# mirsot_sch-final.net
KiCad netlist of a schematic drawn in EAGLE
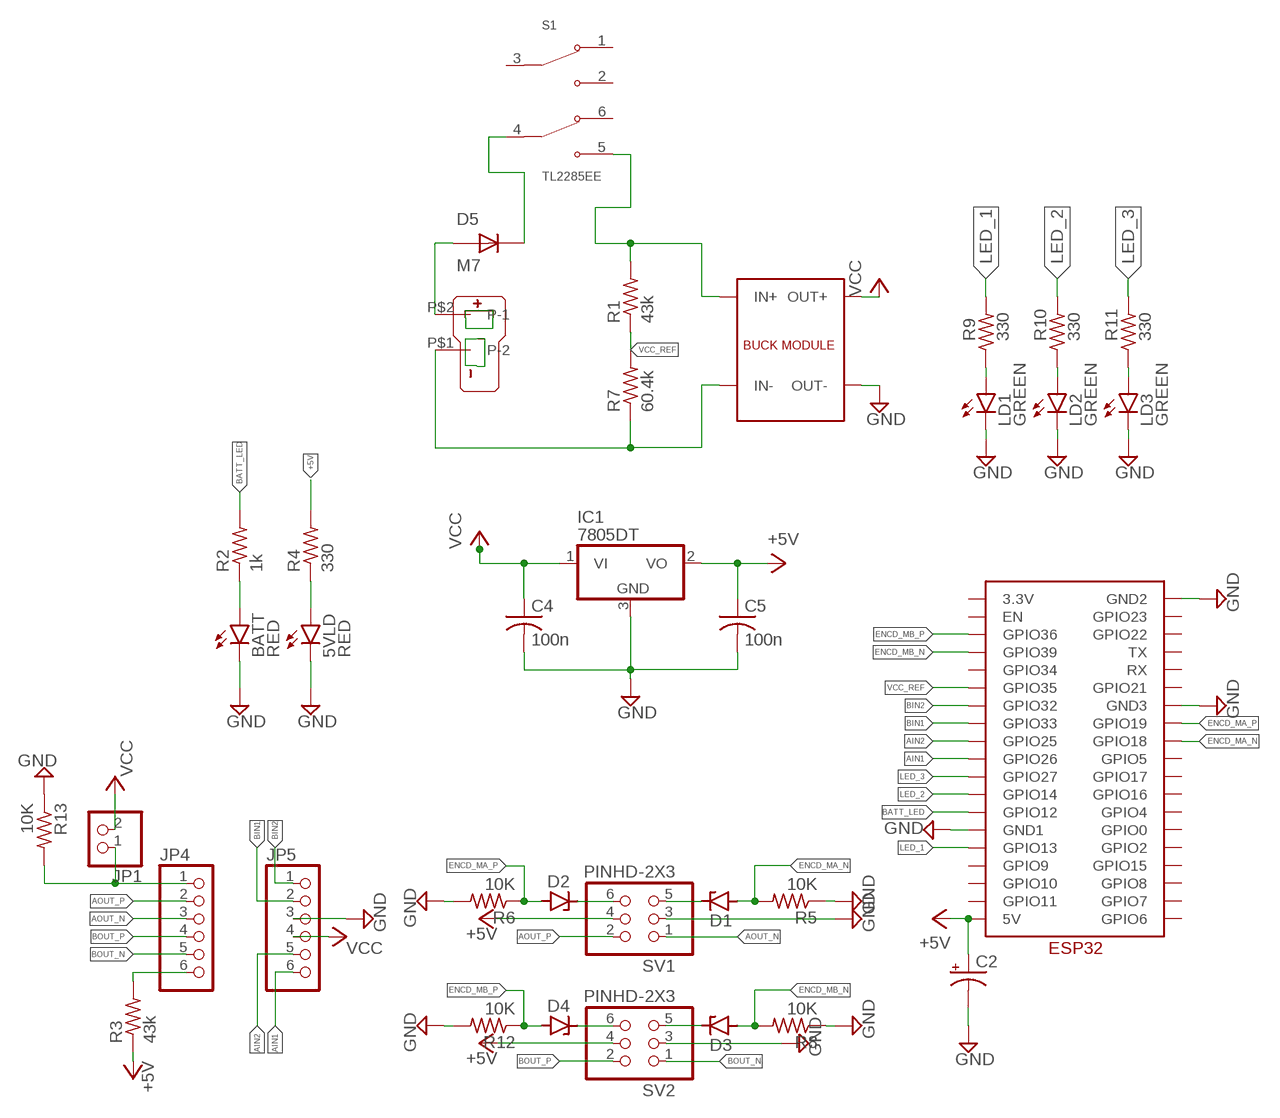
[diagram p0: schematic, sheet 1]

(export (version "E")
  (design (tool "Eeschema 10.0.6"))
  (components
    (comp (ref "5VLD")
      (value "RED")
      (footprint "eagle-import:SML1206")
      (libsource (lib "eagle-import") (part "LEDSML1206"))
    )
    (comp (ref "BATT")
      (value "RED")
      (footprint "eagle-import:SML1206")
      (libsource (lib "eagle-import") (part "LEDSML1206"))
    )
    (comp (ref "C2")
      (value "CPOL-USE2.5-6")
      (footprint "eagle-import:E2,5-6")
      (libsource (lib "eagle-import") (part "CPOL-USE2.5-6"))
    )
    (comp (ref "C4")
      (value "100n")
      (footprint "eagle-import:C0603K")
      (libsource (lib "eagle-import") (part "C-USC0603K"))
    )
    (comp (ref "C5")
      (value "100n")
      (footprint "eagle-import:C0603K")
      (libsource (lib "eagle-import") (part "C-USC0603K"))
    )
    (comp (ref "D1")
      (value "ZENER-DIODEDO34-7")
      (footprint "eagle-import:DO34Z7")
      (libsource (lib "eagle-import") (part "ZENER-DIODEDO34-7"))
    )
    (comp (ref "D2")
      (value "ZENER-DIODEDO34-7")
      (footprint "eagle-import:DO34Z7")
      (libsource (lib "eagle-import") (part "ZENER-DIODEDO34-7"))
    )
    (comp (ref "D3")
      (value "ZENER-DIODEDO34-7")
      (footprint "eagle-import:DO34Z7")
      (libsource (lib "eagle-import") (part "ZENER-DIODEDO34-7"))
    )
    (comp (ref "D4")
      (value "ZENER-DIODEDO34-7")
      (footprint "eagle-import:DO34Z7")
      (libsource (lib "eagle-import") (part "ZENER-DIODEDO34-7"))
    )
    (comp (ref "D5")
      (value "M7")
      (footprint "eagle-import:DIOM505270X240")
      (fields (field (name "MF") "Diotec Semiconductor"))
      (libsource (lib "eagle-import") (part "M7"))
    )
    (comp (ref "IC1")
      (value "7805DT")
      (footprint "eagle-import:TO252")
      (libsource (lib "eagle-import") (part "78DT05"))
    )
    (comp (ref "JP1")
      (value "PINHD-1X2")
      (footprint "eagle-import:1X02")
      (libsource (lib "eagle-import") (part "PINHD-1X2"))
    )
    (comp (ref "JP4")
      (value "PINHD-1X6")
      (footprint "eagle-import:1X06")
      (libsource (lib "eagle-import") (part "PINHD-1X6"))
    )
    (comp (ref "JP5")
      (value "PINHD-1X6")
      (footprint "eagle-import:1X06")
      (libsource (lib "eagle-import") (part "PINHD-1X6"))
    )
    (comp (ref "LD1")
      (value "GREEN")
      (footprint "eagle-import:SML1206")
      (libsource (lib "eagle-import") (part "LEDSML1206"))
    )
    (comp (ref "LD2")
      (value "GREEN")
      (footprint "eagle-import:SML1206")
      (libsource (lib "eagle-import") (part "LEDSML1206"))
    )
    (comp (ref "LD3")
      (value "GREEN")
      (footprint "eagle-import:SML1206")
      (libsource (lib "eagle-import") (part "LEDSML1206"))
    )
    (comp (ref "R1")
      (value "43k")
      (footprint "eagle-import:M1206")
      (libsource (lib "eagle-import") (part "R-US_M1206"))
    )
    (comp (ref "R2")
      (value "1k")
      (footprint "eagle-import:M1206")
      (libsource (lib "eagle-import") (part "R-US_M1206"))
    )
    (comp (ref "R3")
      (value "43k")
      (footprint "eagle-import:M1206")
      (libsource (lib "eagle-import") (part "R-US_M1206"))
    )
    (comp (ref "R4")
      (value "330")
      (footprint "eagle-import:M1206")
      (libsource (lib "eagle-import") (part "R-US_M1206"))
    )
    (comp (ref "R5")
      (value "10K")
      (footprint "eagle-import:M1206")
      (libsource (lib "eagle-import") (part "R-US_M1206"))
    )
    (comp (ref "R6")
      (value "10K")
      (footprint "eagle-import:M1206")
      (libsource (lib "eagle-import") (part "R-US_M1206"))
    )
    (comp (ref "R7")
      (value "60.4k")
      (footprint "eagle-import:M1206")
      (libsource (lib "eagle-import") (part "R-US_M1206"))
    )
    (comp (ref "R8")
      (value "10K")
      (footprint "eagle-import:M1206")
      (libsource (lib "eagle-import") (part "R-US_M1206"))
    )
    (comp (ref "R9")
      (value "330")
      (footprint "eagle-import:M1206")
      (libsource (lib "eagle-import") (part "R-US_M1206"))
    )
    (comp (ref "R10")
      (value "330")
      (footprint "eagle-import:M1206")
      (libsource (lib "eagle-import") (part "R-US_M1206"))
    )
    (comp (ref "R11")
      (value "330")
      (footprint "eagle-import:M1206")
      (libsource (lib "eagle-import") (part "R-US_M1206"))
    )
    (comp (ref "R12")
      (value "10K")
      (footprint "eagle-import:M1206")
      (libsource (lib "eagle-import") (part "R-US_M1206"))
    )
    (comp (ref "R13")
      (value "10K")
      (footprint "eagle-import:M1206")
      (libsource (lib "eagle-import") (part "R-US_M1206"))
    )
    (comp (ref "S1")
      (value "TL2285EE")
      (footprint "eagle-import:SW_TL2285EE")
      (fields (field (name "MF") "E-Switch"))
      (libsource (lib "eagle-import") (part "TL2285EE"))
    )
    (comp (ref "SV1")
      (value "PINHD-2X3")
      (footprint "eagle-import:2X03")
      (libsource (lib "eagle-import") (part "PINHD-2X3"))
    )
    (comp (ref "SV2")
      (value "PINHD-2X3")
      (footprint "eagle-import:2X03")
      (libsource (lib "eagle-import") (part "PINHD-2X3"))
    )
    (comp (ref "U$1")
      (value "T_PLUG_CONNECTOR_H")
      (footprint "eagle-import:T_PLUG_CONNECTOR_H")
      (libsource (lib "eagle-import") (part "T_PLUG_CONNECTOR_H"))
    )
    (comp (ref "U$2")
      (value "ESP32")
      (footprint "eagle-import:ESP32")
      (libsource (lib "eagle-import") (part "ESP32"))
    )
    (comp (ref "U$3")
      (value "BUCK_CONVERTER")
      (footprint "eagle-import:BUCK_CONVERTER")
      (libsource (lib "eagle-import") (part "BUCK_CONVERTER"))
    )
  )
  (nets
    (net (code "1") (name "+5V") (class "Default")
      (node (ref "C2") (pin "+") (pinfunction "+_+") (pintype "passive"))
      (node (ref "C5") (pin "1") (pinfunction "1_1") (pintype "passive"))
      (node (ref "IC1") (pin "2") (pinfunction "VO_2") (pintype "passive"))
      (node (ref "R3") (pin "1") (pinfunction "1_1") (pintype "passive"))
      (node (ref "R4") (pin "2") (pinfunction "2_2") (pintype "passive"))
      (node (ref "SV1") (pin "4") (pinfunction "4_4") (pintype "passive"))
      (node (ref "SV2") (pin "4") (pinfunction "4_4") (pintype "passive"))
      (node (ref "U$2") (pin "5V") (pinfunction "5V_5V") (pintype "bidirectional"))
    )
    (net (code "2") (name "AIN1") (class "Default")
      (node (ref "JP5") (pin "6") (pinfunction "6_6") (pintype "passive"))
      (node (ref "U$2") (pin "GPIO26") (pinfunction "GPIO26_GPIO26") (pintype "bidirectional"))
    )
    (net (code "3") (name "AIN2") (class "Default")
      (node (ref "JP5") (pin "5") (pinfunction "5_5") (pintype "passive"))
      (node (ref "U$2") (pin "GPIO25") (pinfunction "GPIO25_GPIO25") (pintype "bidirectional"))
    )
    (net (code "4") (name "AOUT_N") (class "Default")
      (node (ref "JP4") (pin "3") (pinfunction "3_3") (pintype "passive"))
      (node (ref "SV1") (pin "1") (pinfunction "1_1") (pintype "passive"))
    )
    (net (code "5") (name "AOUT_P") (class "Default")
      (node (ref "JP4") (pin "2") (pinfunction "2_2") (pintype "passive"))
      (node (ref "SV1") (pin "2") (pinfunction "2_2") (pintype "passive"))
    )
    (net (code "6") (name "BATT_LED") (class "Default")
      (node (ref "R2") (pin "2") (pinfunction "2_2") (pintype "passive"))
      (node (ref "U$2") (pin "GPIO12") (pinfunction "GPIO12_GPIO12") (pintype "bidirectional"))
    )
    (net (code "7") (name "BIN1") (class "Default")
      (node (ref "JP5") (pin "2") (pinfunction "2_2") (pintype "passive"))
      (node (ref "U$2") (pin "GPIO33") (pinfunction "GPIO33_GPIO33") (pintype "bidirectional"))
    )
    (net (code "8") (name "BIN2") (class "Default")
      (node (ref "JP5") (pin "1") (pinfunction "1_1") (pintype "passive"))
      (node (ref "U$2") (pin "GPIO32") (pinfunction "GPIO32_GPIO32") (pintype "bidirectional"))
    )
    (net (code "9") (name "BOUT_N") (class "Default")
      (node (ref "JP4") (pin "5") (pinfunction "5_5") (pintype "passive"))
      (node (ref "SV2") (pin "1") (pinfunction "1_1") (pintype "passive"))
    )
    (net (code "10") (name "BOUT_P") (class "Default")
      (node (ref "JP4") (pin "4") (pinfunction "4_4") (pintype "passive"))
      (node (ref "SV2") (pin "2") (pinfunction "2_2") (pintype "passive"))
    )
    (net (code "11") (name "ENCD_MA_N") (class "Default")
      (node (ref "D1") (pin "A") (pinfunction "A_A") (pintype "passive"))
      (node (ref "R5") (pin "2") (pinfunction "2_2") (pintype "passive"))
      (node (ref "U$2") (pin "GPIO18") (pinfunction "GPIO18_GPIO18") (pintype "bidirectional"))
    )
    (net (code "12") (name "ENCD_MA_P") (class "Default")
      (node (ref "D2") (pin "A") (pinfunction "A_A") (pintype "passive"))
      (node (ref "R6") (pin "1") (pinfunction "1_1") (pintype "passive"))
      (node (ref "U$2") (pin "GPIO19") (pinfunction "GPIO19_GPIO19") (pintype "bidirectional"))
    )
    (net (code "13") (name "ENCD_MB_N") (class "Default")
      (node (ref "D3") (pin "A") (pinfunction "A_A") (pintype "passive"))
      (node (ref "R8") (pin "2") (pinfunction "2_2") (pintype "passive"))
      (node (ref "U$2") (pin "GPIO39") (pinfunction "GPIO39_GPIO39") (pintype "bidirectional"))
    )
    (net (code "14") (name "ENCD_MB_P") (class "Default")
      (node (ref "D4") (pin "A") (pinfunction "A_A") (pintype "passive"))
      (node (ref "R12") (pin "1") (pinfunction "1_1") (pintype "passive"))
      (node (ref "U$2") (pin "GPIO36") (pinfunction "GPIO36_GPIO36") (pintype "bidirectional"))
    )
    (net (code "15") (name "GND") (class "Default")
      (node (ref "5VLD") (pin "C") (pinfunction "C_C") (pintype "passive"))
      (node (ref "BATT") (pin "C") (pinfunction "C_C") (pintype "passive"))
      (node (ref "C2") (pin "-") (pinfunction "-_-") (pintype "passive"))
      (node (ref "C4") (pin "2") (pinfunction "2_2") (pintype "passive"))
      (node (ref "C5") (pin "2") (pinfunction "2_2") (pintype "passive"))
      (node (ref "IC1") (pin "3") (pinfunction "GND_3") (pintype "passive"))
      (node (ref "JP5") (pin "3") (pinfunction "3_3") (pintype "passive"))
      (node (ref "LD1") (pin "C") (pinfunction "C_C") (pintype "passive"))
      (node (ref "LD2") (pin "C") (pinfunction "C_C") (pintype "passive"))
      (node (ref "LD3") (pin "C") (pinfunction "C_C") (pintype "passive"))
      (node (ref "R12") (pin "2") (pinfunction "2_2") (pintype "passive"))
      (node (ref "R13") (pin "1") (pinfunction "1_1") (pintype "passive"))
      (node (ref "R5") (pin "1") (pinfunction "1_1") (pintype "passive"))
      (node (ref "R6") (pin "2") (pinfunction "2_2") (pintype "passive"))
      (node (ref "R8") (pin "1") (pinfunction "1_1") (pintype "passive"))
      (node (ref "SV1") (pin "3") (pinfunction "3_3") (pintype "passive"))
      (node (ref "SV2") (pin "3") (pinfunction "3_3") (pintype "passive"))
      (node (ref "U$2") (pin "GND1") (pinfunction "GND1_GND1") (pintype "bidirectional"))
      (node (ref "U$2") (pin "GND2") (pinfunction "GND2_GND2") (pintype "bidirectional"))
      (node (ref "U$2") (pin "GND3") (pinfunction "GND3_GND3") (pintype "bidirectional"))
      (node (ref "U$3") (pin "OUT-") (pinfunction "OUT-_OUT-") (pintype "bidirectional"))
    )
    (net (code "16") (name "LED_1") (class "Default")
      (node (ref "R9") (pin "2") (pinfunction "2_2") (pintype "passive"))
      (node (ref "U$2") (pin "GPIO13") (pinfunction "GPIO13_GPIO13") (pintype "bidirectional"))
    )
    (net (code "17") (name "LED_2") (class "Default")
      (node (ref "R10") (pin "2") (pinfunction "2_2") (pintype "passive"))
      (node (ref "U$2") (pin "GPIO14") (pinfunction "GPIO14_GPIO14") (pintype "bidirectional"))
    )
    (net (code "18") (name "LED_3") (class "Default")
      (node (ref "R11") (pin "2") (pinfunction "2_2") (pintype "passive"))
      (node (ref "U$2") (pin "GPIO27") (pinfunction "GPIO27_GPIO27") (pintype "bidirectional"))
    )
    (net (code "19") (name "Net-(5VLD-PadA)") (class "Default")
      (node (ref "5VLD") (pin "A") (pinfunction "A_A") (pintype "passive"))
      (node (ref "R4") (pin "1") (pinfunction "1_1") (pintype "passive"))
    )
    (net (code "20") (name "Net-(BATT-PadA)") (class "Default")
      (node (ref "BATT") (pin "A") (pinfunction "A_A") (pintype "passive"))
      (node (ref "R2") (pin "1") (pinfunction "1_1") (pintype "passive"))
    )
    (net (code "21") (name "Net-(D1-PadC)") (class "Default")
      (node (ref "D1") (pin "C") (pinfunction "C_C") (pintype "passive"))
      (node (ref "SV1") (pin "5") (pinfunction "5_5") (pintype "passive"))
    )
    (net (code "22") (name "Net-(D2-PadC)") (class "Default")
      (node (ref "D2") (pin "C") (pinfunction "C_C") (pintype "passive"))
      (node (ref "SV1") (pin "6") (pinfunction "6_6") (pintype "passive"))
    )
    (net (code "23") (name "Net-(D3-PadC)") (class "Default")
      (node (ref "D3") (pin "C") (pinfunction "C_C") (pintype "passive"))
      (node (ref "SV2") (pin "5") (pinfunction "5_5") (pintype "passive"))
    )
    (net (code "24") (name "Net-(D4-PadC)") (class "Default")
      (node (ref "D4") (pin "C") (pinfunction "C_C") (pintype "passive"))
      (node (ref "SV2") (pin "6") (pinfunction "6_6") (pintype "passive"))
    )
    (net (code "25") (name "Net-(JP1-Pad1)") (class "Default")
      (node (ref "JP1") (pin "1") (pinfunction "1_1") (pintype "passive"))
      (node (ref "JP4") (pin "1") (pinfunction "1_1") (pintype "passive"))
      (node (ref "R13") (pin "2") (pinfunction "2_2") (pintype "passive"))
    )
    (net (code "26") (name "Net-(JP4-Pad6)") (class "Default")
      (node (ref "JP4") (pin "6") (pinfunction "6_6") (pintype "passive"))
      (node (ref "R3") (pin "2") (pinfunction "2_2") (pintype "passive"))
    )
    (net (code "27") (name "Net-(LD1-PadA)") (class "Default")
      (node (ref "LD1") (pin "A") (pinfunction "A_A") (pintype "passive"))
      (node (ref "R9") (pin "1") (pinfunction "1_1") (pintype "passive"))
    )
    (net (code "28") (name "Net-(LD2-PadA)") (class "Default")
      (node (ref "LD2") (pin "A") (pinfunction "A_A") (pintype "passive"))
      (node (ref "R10") (pin "1") (pinfunction "1_1") (pintype "passive"))
    )
    (net (code "29") (name "Net-(LD3-PadA)") (class "Default")
      (node (ref "LD3") (pin "A") (pinfunction "A_A") (pintype "passive"))
      (node (ref "R11") (pin "1") (pinfunction "1_1") (pintype "passive"))
    )
    (net (code "30") (name "Net-(S1-COM2)") (class "Default")
      (node (ref "D5") (pin "C") (pinfunction "C_C") (pintype "passive"))
      (node (ref "S1") (pin "4") (pinfunction "COM2_4") (pintype "passive"))
    )
    (net (code "31") (name "Net-(S1-NO2)") (class "Default")
      (node (ref "R1") (pin "2") (pinfunction "2_2") (pintype "passive"))
      (node (ref "S1") (pin "5") (pinfunction "NO2_5") (pintype "passive"))
      (node (ref "U$3") (pin "IN+") (pinfunction "IN+_IN+") (pintype "bidirectional"))
    )
    (net (code "32") (name "Net-(U$1-P-1)") (class "Default")
      (node (ref "D5") (pin "A") (pinfunction "A_A") (pintype "passive"))
      (node (ref "U$1") (pin "P$2") (pinfunction "P-1_P$2") (pintype "passive"))
    )
    (net (code "33") (name "Net-(U$1-P-2)") (class "Default")
      (node (ref "R7") (pin "1") (pinfunction "1_1") (pintype "passive"))
      (node (ref "U$1") (pin "P$1") (pinfunction "P-2_P$1") (pintype "passive"))
      (node (ref "U$3") (pin "IN-") (pinfunction "IN-_IN-") (pintype "bidirectional"))
    )
    (net (code "34") (name "VCC") (class "Default")
      (node (ref "C4") (pin "1") (pinfunction "1_1") (pintype "passive"))
      (node (ref "IC1") (pin "1") (pinfunction "VI_1") (pintype "input"))
      (node (ref "JP1") (pin "2") (pinfunction "2_2") (pintype "passive"))
      (node (ref "JP5") (pin "4") (pinfunction "4_4") (pintype "passive"))
      (node (ref "U$3") (pin "OUT+") (pinfunction "OUT+_OUT+") (pintype "bidirectional"))
    )
    (net (code "35") (name "VCC_REF") (class "Default")
      (node (ref "R1") (pin "1") (pinfunction "1_1") (pintype "passive"))
      (node (ref "R7") (pin "2") (pinfunction "2_2") (pintype "passive"))
      (node (ref "U$2") (pin "GPIO35") (pinfunction "GPIO35_GPIO35") (pintype "bidirectional"))
    )
    (net (code "36") (name "unconnected-(S1-COM1-Pad3)") (class "Default")
      (node (ref "S1") (pin "3") (pinfunction "COM1_3") (pintype "passive"))
    )
    (net (code "37") (name "unconnected-(S1-NC1-Pad1)") (class "Default")
      (node (ref "S1") (pin "1") (pinfunction "NC1_1") (pintype "passive"))
    )
    (net (code "38") (name "unconnected-(S1-NC2-Pad6)") (class "Default")
      (node (ref "S1") (pin "6") (pinfunction "NC2_6") (pintype "passive"))
    )
    (net (code "39") (name "unconnected-(S1-NO1-Pad2)") (class "Default")
      (node (ref "S1") (pin "2") (pinfunction "NO1_2") (pintype "passive"))
    )
    (net (code "40") (name "unconnected-(U$2-Pad3.3V)") (class "Default")
      (node (ref "U$2") (pin "3.3V") (pinfunction "3.3V_3.3V") (pintype "bidirectional"))
    )
    (net (code "41") (name "unconnected-(U$2-PadEN)") (class "Default")
      (node (ref "U$2") (pin "EN") (pinfunction "EN_EN") (pintype "bidirectional"))
    )
    (net (code "42") (name "unconnected-(U$2-PadGPIO0)") (class "Default")
      (node (ref "U$2") (pin "GPIO0") (pinfunction "GPIO0_GPIO0") (pintype "bidirectional"))
    )
    (net (code "43") (name "unconnected-(U$2-PadGPIO2)") (class "Default")
      (node (ref "U$2") (pin "GPIO2") (pinfunction "GPIO2_GPIO2") (pintype "bidirectional"))
    )
    (net (code "44") (name "unconnected-(U$2-PadGPIO4)") (class "Default")
      (node (ref "U$2") (pin "GPIO4") (pinfunction "GPIO4_GPIO4") (pintype "bidirectional"))
    )
    (net (code "45") (name "unconnected-(U$2-PadGPIO5)") (class "Default")
      (node (ref "U$2") (pin "GPIO5") (pinfunction "GPIO5_GPIO5") (pintype "bidirectional"))
    )
    (net (code "46") (name "unconnected-(U$2-PadGPIO6)") (class "Default")
      (node (ref "U$2") (pin "GPIO6") (pinfunction "GPIO6_GPIO6") (pintype "bidirectional"))
    )
    (net (code "47") (name "unconnected-(U$2-PadGPIO7)") (class "Default")
      (node (ref "U$2") (pin "GPIO7") (pinfunction "GPIO7_GPIO7") (pintype "bidirectional"))
    )
    (net (code "48") (name "unconnected-(U$2-PadGPIO8)") (class "Default")
      (node (ref "U$2") (pin "GPIO8") (pinfunction "GPIO8_GPIO8") (pintype "bidirectional"))
    )
    (net (code "49") (name "unconnected-(U$2-PadGPIO9)") (class "Default")
      (node (ref "U$2") (pin "GPIO9") (pinfunction "GPIO9_GPIO9") (pintype "bidirectional"))
    )
    (net (code "50") (name "unconnected-(U$2-PadGPIO10)") (class "Default")
      (node (ref "U$2") (pin "GPIO10") (pinfunction "GPIO10_GPIO10") (pintype "bidirectional"))
    )
    (net (code "51") (name "unconnected-(U$2-PadGPIO11)") (class "Default")
      (node (ref "U$2") (pin "GPIO11") (pinfunction "GPIO11_GPIO11") (pintype "bidirectional"))
    )
    (net (code "52") (name "unconnected-(U$2-PadGPIO15)") (class "Default")
      (node (ref "U$2") (pin "GPIO15") (pinfunction "GPIO15_GPIO15") (pintype "bidirectional"))
    )
    (net (code "53") (name "unconnected-(U$2-PadGPIO16)") (class "Default")
      (node (ref "U$2") (pin "GPIO16") (pinfunction "GPIO16_GPIO16") (pintype "bidirectional"))
    )
    (net (code "54") (name "unconnected-(U$2-PadGPIO17)") (class "Default")
      (node (ref "U$2") (pin "GPIO17") (pinfunction "GPIO17_GPIO17") (pintype "bidirectional"))
    )
    (net (code "55") (name "unconnected-(U$2-PadGPIO21)") (class "Default")
      (node (ref "U$2") (pin "GPIO21") (pinfunction "GPIO21_GPIO21") (pintype "bidirectional"))
    )
    (net (code "56") (name "unconnected-(U$2-PadGPIO22)") (class "Default")
      (node (ref "U$2") (pin "GPIO22") (pinfunction "GPIO22_GPIO22") (pintype "bidirectional"))
    )
    (net (code "57") (name "unconnected-(U$2-PadGPIO23)") (class "Default")
      (node (ref "U$2") (pin "GPIO23") (pinfunction "GPIO23_GPIO23") (pintype "bidirectional"))
    )
    (net (code "58") (name "unconnected-(U$2-PadGPIO34)") (class "Default")
      (node (ref "U$2") (pin "GPIO34") (pinfunction "GPIO34_GPIO34") (pintype "bidirectional"))
    )
    (net (code "59") (name "unconnected-(U$2-PadRX)") (class "Default")
      (node (ref "U$2") (pin "RX") (pinfunction "RX_RX") (pintype "bidirectional"))
    )
    (net (code "60") (name "unconnected-(U$2-PadTX)") (class "Default")
      (node (ref "U$2") (pin "TX") (pinfunction "TX_TX") (pintype "bidirectional"))
    )
  )
)
